# buck3.net
KiCad netlist of a schematic drawn in Altium Designer
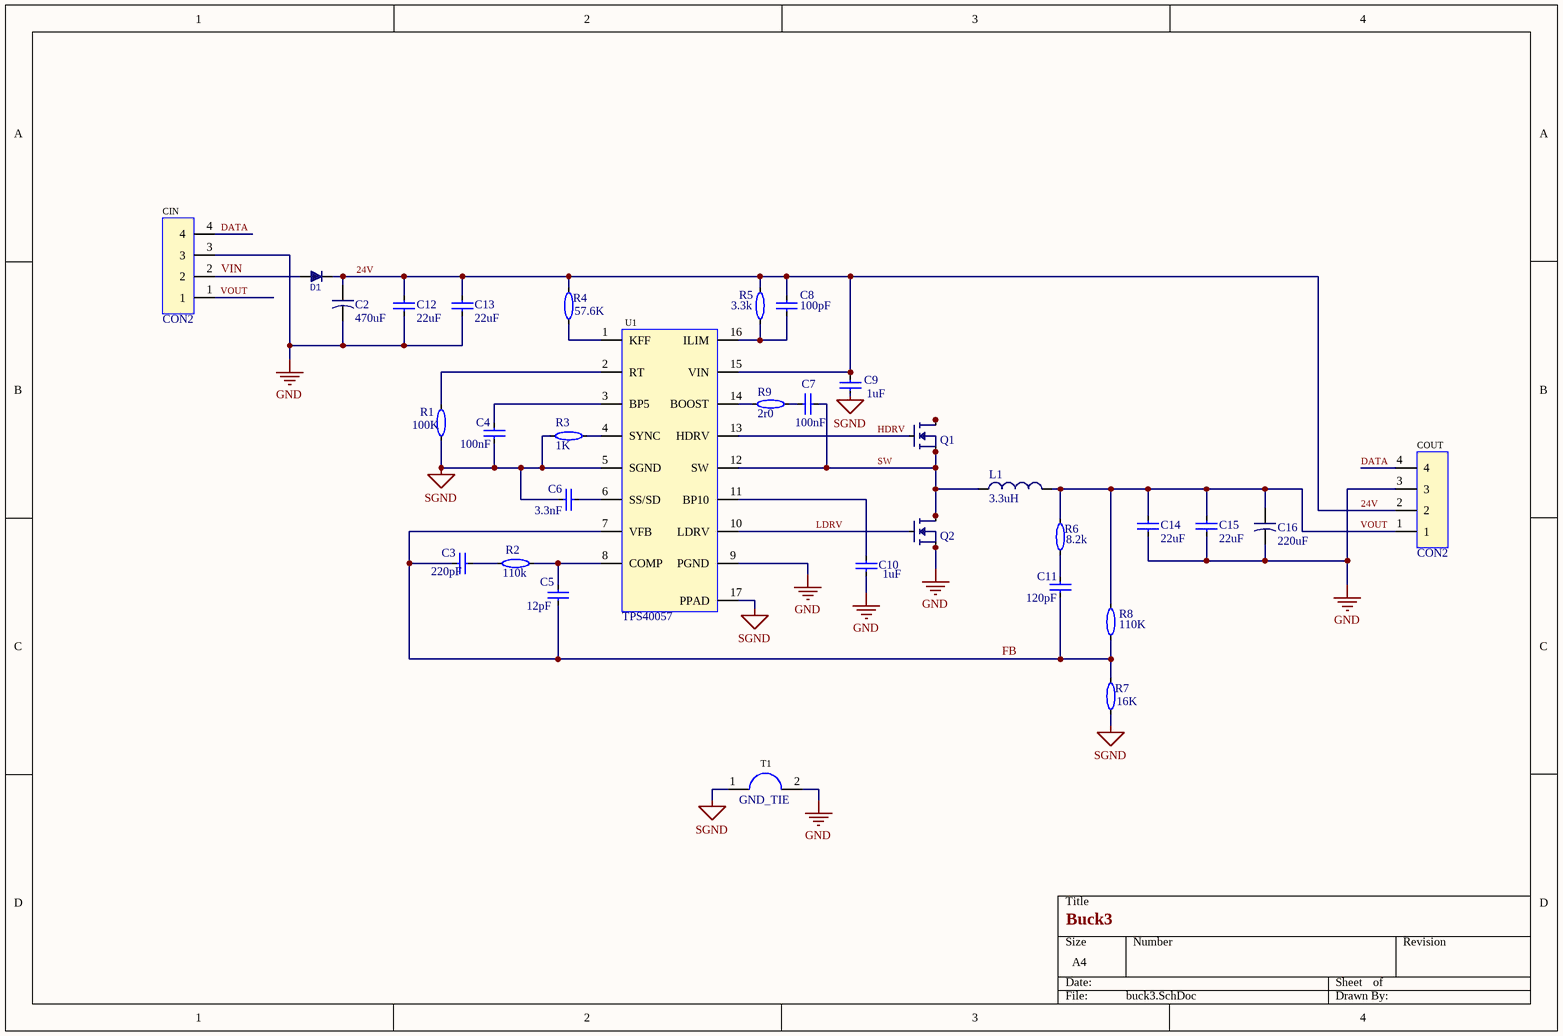
[diagram p0: buck3.SchDoc]

(export (version "E")
  (design (tool "Eeschema 10.0.6"))
  (components
    (comp (ref "C2")
      (value "470uF")
      (footprint "CAPAE110103X125L")
      (description "Capacitor")
      (libsource (lib "buck3") (part "E CAP"))
    )
    (comp (ref "C3")
      (value "220pF")
      (footprint "CAPC 0603 1608X05L")
      (description "Capacitor")
      (fields (field (name "PUBLISHER") "Altium Limited"))
      (libsource (lib "buck3") (part "Cap"))
    )
    (comp (ref "C4")
      (value "100nF")
      (footprint "CAPC 0603 1608X05L")
      (description "Capacitor")
      (fields (field (name "PUBLISHER") "Altium Limited"))
      (libsource (lib "buck3") (part "Cap"))
    )
    (comp (ref "C5")
      (value "12pF")
      (footprint "CAPC 0603 1608X05L")
      (description "Capacitor")
      (fields (field (name "PUBLISHER") "Altium Limited"))
      (libsource (lib "buck3") (part "Cap"))
    )
    (comp (ref "C6")
      (value "3.3nF")
      (footprint "CAPC 0603 1608X05L")
      (description "Capacitor")
      (fields (field (name "PUBLISHER") "Altium Limited"))
      (libsource (lib "buck3") (part "Cap"))
    )
    (comp (ref "C7")
      (value "100nF")
      (footprint "CAPC 0603 1608X05L")
      (description "Capacitor")
      (fields (field (name "PUBLISHER") "Altium Limited"))
      (libsource (lib "buck3") (part "Cap"))
    )
    (comp (ref "C8")
      (value "100pF")
      (footprint "CAPC 0603 1608X05L")
      (description "Capacitor")
      (fields (field (name "PUBLISHER") "Altium Limited"))
      (libsource (lib "buck3") (part "Cap"))
    )
    (comp (ref "C9")
      (value "1uF")
      (footprint "CAPC 0603 1608X05L")
      (description "Capacitor")
      (fields (field (name "PUBLISHER") "Altium Limited"))
      (libsource (lib "buck3") (part "Cap"))
    )
    (comp (ref "C10")
      (value "1uF")
      (footprint "CAPC 0603 1608X05L")
      (description "Capacitor")
      (fields (field (name "PUBLISHER") "Altium Limited"))
      (libsource (lib "buck3") (part "Cap"))
    )
    (comp (ref "C11")
      (value "120pF")
      (footprint "CAPC 0603 1608X05L")
      (description "Capacitor")
      (fields (field (name "PUBLISHER") "Altium Limited"))
      (libsource (lib "buck3") (part "Cap"))
    )
    (comp (ref "C12")
      (value "22uF")
      (footprint "CAPC 1210")
      (description "Capacitor")
      (fields (field (name "PUBLISHER") "Altium Limited"))
      (libsource (lib "buck3") (part "Cap"))
    )
    (comp (ref "C13")
      (value "22uF")
      (footprint "CAPC 1210")
      (description "Capacitor")
      (fields (field (name "PUBLISHER") "Altium Limited"))
      (libsource (lib "buck3") (part "Cap"))
    )
    (comp (ref "C14")
      (value "22uF")
      (footprint "CAPC 1210")
      (description "Capacitor")
      (fields (field (name "PUBLISHER") "Altium Limited"))
      (libsource (lib "buck3") (part "Cap"))
    )
    (comp (ref "C15")
      (value "22uF")
      (footprint "CAPC 1210")
      (description "Capacitor")
      (fields (field (name "PUBLISHER") "Altium Limited"))
      (libsource (lib "buck3") (part "Cap"))
    )
    (comp (ref "C16")
      (value "220uF")
      (footprint "CAPAE110103X125L")
      (description "Capacitor")
      (libsource (lib "buck3") (part "E CAP"))
    )
    (comp (ref "CIN") (value "CON2") (footprint "CON2") (libsource (lib "buck3") (part "CON2")))
    (comp (ref "COUT") (value "CON2") (footprint "CON2") (libsource (lib "") (part "CON2_1")))
    (comp (ref "D1") (value "DIODE") (footprint "SODFL350X110-2N") (libsource (lib "buck3") (part "DIODE")))
    (comp (ref "L1")
      (value "3.3uH")
      (footprint "INDP135126X40L")
      (description "Inductor")
      (fields (field (name "PUBLISHER") "Altium Limited"))
      (libsource (lib "buck3") (part "Inductor"))
    )
    (comp (ref "Q1")
      (value "Infineon BSC093N04LSGATMA1")
      (footprint "INF-PG-TDSON-8-1_V")
      (description "N Channel MOSFET")
      (libsource (lib "buck3") (part "MOSFET-N"))
    )
    (comp (ref "Q2")
      (value "Infineon BSC093N04LSGATMA1")
      (footprint "INF-PG-TDSON-8-1_V")
      (description "N Channel MOSFET")
      (libsource (lib "buck3") (part "MOSFET-N"))
    )
    (comp (ref "R1")
      (value "100K")
      (footprint "RESC 0603 1608X05L")
      (description "Resistor")
      (fields (field (name "PUBLISHER") "Altium Limited"))
      (libsource (lib "buck3") (part "Res2"))
    )
    (comp (ref "R2")
      (value "110k")
      (footprint "RESC 0603 1608X05L")
      (description "Resistor")
      (fields (field (name "PUBLISHER") "Altium Limited"))
      (libsource (lib "buck3") (part "Res2"))
    )
    (comp (ref "R3")
      (value "1K")
      (footprint "RESC 0603 1608X05L")
      (description "Resistor")
      (fields (field (name "PUBLISHER") "Altium Limited"))
      (libsource (lib "buck3") (part "Res2"))
    )
    (comp (ref "R4")
      (value "57.6K")
      (footprint "RESC 0603 1608X05L")
      (description "Resistor")
      (fields (field (name "PUBLISHER") "Altium Limited"))
      (libsource (lib "buck3") (part "Res2"))
    )
    (comp (ref "R5")
      (value "3.3k")
      (footprint "RESC 0603 1608X05L")
      (description "Resistor")
      (fields (field (name "PUBLISHER") "Altium Limited"))
      (libsource (lib "buck3") (part "Res2"))
    )
    (comp (ref "R6")
      (value "8.2k")
      (footprint "RESC 0603 1608X05L")
      (description "Resistor")
      (fields (field (name "PUBLISHER") "Altium Limited"))
      (libsource (lib "buck3") (part "Res2"))
    )
    (comp (ref "R7")
      (value "16K")
      (footprint "RESC 0603 1608X05L")
      (description "Resistor")
      (fields (field (name "PUBLISHER") "Altium Limited"))
      (libsource (lib "buck3") (part "Res2"))
    )
    (comp (ref "R8")
      (value "110K")
      (footprint "RESC 0603 1608X05L")
      (description "Resistor")
      (fields (field (name "PUBLISHER") "Altium Limited"))
      (libsource (lib "buck3") (part "Res2"))
    )
    (comp (ref "R9")
      (value "2r0")
      (footprint "RESC 0603 1608X05L")
      (description "Resistor")
      (fields (field (name "PUBLISHER") "Altium Limited"))
      (libsource (lib "buck3") (part "Res2"))
    )
    (comp (ref "T1") (value "GND_TIE") (footprint "GND_TIE") (libsource (lib "buck3") (part "GND_TIE")))
    (comp (ref "U1")
      (value "TPS40057")
      (footprint "TSOP65P640X120_HS-17N")
      (description "Buck Controller")
      (libsource (lib "buck3") (part "TPS40057"))
    )
  )
  (nets
    (net (code "1") (name "/24V") (class "Default")
      (node (ref "C12") (pin "2") (pinfunction "2_2") (pintype "passive"))
      (node (ref "C13") (pin "2") (pinfunction "2_2") (pintype "passive"))
      (node (ref "C2") (pin "1") (pinfunction "1_1") (pintype "passive"))
      (node (ref "C8") (pin "2") (pinfunction "2_2") (pintype "passive"))
      (node (ref "C9") (pin "2") (pinfunction "2_2") (pintype "passive"))
      (node (ref "COUT") (pin "2") (pinfunction "2_2") (pintype "passive"))
      (node (ref "D1") (pin "1") (pinfunction "CATHODE_1") (pintype "power_in"))
      (node (ref "R4") (pin "1") (pinfunction "1_1") (pintype "passive"))
      (node (ref "R5") (pin "1") (pinfunction "1_1") (pintype "passive"))
      (node (ref "U1") (pin "15") (pinfunction "VIN_15") (pintype "passive"))
    )
    (net (code "2") (name "/DATA") (class "Default")
      (node (ref "CIN") (pin "4") (pinfunction "4_4") (pintype "passive"))
      (node (ref "COUT") (pin "4") (pinfunction "4_4") (pintype "passive"))
    )
    (net (code "3") (name "/FB") (class "Default")
      (node (ref "C11") (pin "2") (pinfunction "2_2") (pintype "passive"))
      (node (ref "C3") (pin "2") (pinfunction "2_2") (pintype "passive"))
      (node (ref "C5") (pin "2") (pinfunction "2_2") (pintype "passive"))
      (node (ref "R7") (pin "2") (pinfunction "2_2") (pintype "passive"))
      (node (ref "R8") (pin "1") (pinfunction "1_1") (pintype "passive"))
      (node (ref "U1") (pin "7") (pinfunction "VFB_7") (pintype "passive"))
    )
    (net (code "4") (name "/HDRV") (class "Default")
      (node (ref "Q1") (pin "4") (pinfunction "G_4") (pintype "passive"))
      (node (ref "U1") (pin "13") (pinfunction "HDRV_13") (pintype "passive"))
    )
    (net (code "5") (name "/LDRV") (class "Default")
      (node (ref "Q2") (pin "4") (pinfunction "G_4") (pintype "passive"))
      (node (ref "U1") (pin "10") (pinfunction "LDRV_10") (pintype "passive"))
    )
    (net (code "6") (name "/SW") (class "Default")
      (node (ref "C7") (pin "1") (pinfunction "1_1") (pintype "passive"))
      (node (ref "L1") (pin "1") (pinfunction "1_1") (pintype "passive"))
      (node (ref "Q1") (pin "1") (pinfunction "S_1") (pintype "passive"))
      (node (ref "Q1") (pin "2") (pinfunction "S_2") (pintype "passive"))
      (node (ref "Q1") (pin "3") (pinfunction "S_3") (pintype "passive"))
      (node (ref "Q2") (pin "5") (pinfunction "D_5") (pintype "passive"))
      (node (ref "Q2") (pin "6") (pinfunction "D_6") (pintype "passive"))
      (node (ref "Q2") (pin "7") (pinfunction "D_7") (pintype "passive"))
      (node (ref "Q2") (pin "8") (pinfunction "8_8") (pintype "passive"))
      (node (ref "U1") (pin "12") (pinfunction "SW_12") (pintype "passive"))
    )
    (net (code "7") (name "/VIN") (class "Default")
      (node (ref "CIN") (pin "2") (pinfunction "2_2") (pintype "passive"))
      (node (ref "D1") (pin "2") (pinfunction "ANODE_2") (pintype "power_in"))
    )
    (net (code "8") (name "/VOUT") (class "Default")
      (node (ref "C14") (pin "2") (pinfunction "2_2") (pintype "passive"))
      (node (ref "C15") (pin "2") (pinfunction "2_2") (pintype "passive"))
      (node (ref "C16") (pin "1") (pinfunction "1_1") (pintype "passive"))
      (node (ref "CIN") (pin "1") (pinfunction "1_1") (pintype "passive"))
      (node (ref "COUT") (pin "1") (pinfunction "1_1") (pintype "passive"))
      (node (ref "L1") (pin "2") (pinfunction "2_2") (pintype "passive"))
      (node (ref "R6") (pin "2") (pinfunction "2_2") (pintype "passive"))
      (node (ref "R8") (pin "2") (pinfunction "2_2") (pintype "passive"))
    )
    (net (code "9") (name "GND") (class "Default")
      (node (ref "C10") (pin "1") (pinfunction "1_1") (pintype "passive"))
      (node (ref "C12") (pin "1") (pinfunction "1_1") (pintype "passive"))
      (node (ref "C13") (pin "1") (pinfunction "1_1") (pintype "passive"))
      (node (ref "C14") (pin "1") (pinfunction "1_1") (pintype "passive"))
      (node (ref "C15") (pin "1") (pinfunction "1_1") (pintype "passive"))
      (node (ref "C16") (pin "2") (pinfunction "2_2") (pintype "passive"))
      (node (ref "C2") (pin "2") (pinfunction "2_2") (pintype "passive"))
      (node (ref "CIN") (pin "3") (pinfunction "3_3") (pintype "passive"))
      (node (ref "COUT") (pin "3") (pinfunction "3_3") (pintype "passive"))
      (node (ref "Q2") (pin "1") (pinfunction "S_1") (pintype "passive"))
      (node (ref "Q2") (pin "2") (pinfunction "S_2") (pintype "passive"))
      (node (ref "Q2") (pin "3") (pinfunction "S_3") (pintype "passive"))
      (node (ref "T1") (pin "2") (pinfunction "2_2") (pintype "passive"))
      (node (ref "U1") (pin "9") (pinfunction "PGND_9") (pintype "passive"))
    )
    (net (code "10") (name "Net-(C3-Pad1)") (class "Default")
      (node (ref "C3") (pin "1") (pinfunction "1_1") (pintype "passive"))
      (node (ref "R2") (pin "1") (pinfunction "1_1") (pintype "passive"))
    )
    (net (code "11") (name "Net-(C7-Pad2)") (class "Default")
      (node (ref "C7") (pin "2") (pinfunction "2_2") (pintype "passive"))
      (node (ref "R9") (pin "2") (pinfunction "2_2") (pintype "passive"))
    )
    (net (code "12") (name "Net-(C11-Pad1)") (class "Default")
      (node (ref "C11") (pin "1") (pinfunction "1_1") (pintype "passive"))
      (node (ref "R6") (pin "1") (pinfunction "1_1") (pintype "passive"))
    )
    (net (code "13") (name "Net-(Q1-D-Pad5)") (class "Default")
      (node (ref "Q1") (pin "5") (pinfunction "D_5") (pintype "passive"))
      (node (ref "Q1") (pin "6") (pinfunction "D_6") (pintype "passive"))
      (node (ref "Q1") (pin "7") (pinfunction "D_7") (pintype "passive"))
      (node (ref "Q1") (pin "8") (pinfunction "8_8") (pintype "passive"))
    )
    (net (code "14") (name "Net-(U1-BOOST)") (class "Default")
      (node (ref "R9") (pin "1") (pinfunction "1_1") (pintype "passive"))
      (node (ref "U1") (pin "14") (pinfunction "BOOST_14") (pintype "passive"))
    )
    (net (code "15") (name "Net-(U1-BP5)") (class "Default")
      (node (ref "C4") (pin "2") (pinfunction "2_2") (pintype "passive"))
      (node (ref "U1") (pin "3") (pinfunction "BP5_3") (pintype "passive"))
    )
    (net (code "16") (name "Net-(U1-BP10)") (class "Default")
      (node (ref "C10") (pin "2") (pinfunction "2_2") (pintype "passive"))
      (node (ref "U1") (pin "11") (pinfunction "BP10_11") (pintype "passive"))
    )
    (net (code "17") (name "Net-(U1-COMP)") (class "Default")
      (node (ref "C5") (pin "1") (pinfunction "1_1") (pintype "passive"))
      (node (ref "R2") (pin "2") (pinfunction "2_2") (pintype "passive"))
      (node (ref "U1") (pin "8") (pinfunction "COMP_8") (pintype "passive"))
    )
    (net (code "18") (name "Net-(U1-ILIM)") (class "Default")
      (node (ref "C8") (pin "1") (pinfunction "1_1") (pintype "passive"))
      (node (ref "R5") (pin "2") (pinfunction "2_2") (pintype "passive"))
      (node (ref "U1") (pin "16") (pinfunction "ILIM_16") (pintype "passive"))
    )
    (net (code "19") (name "Net-(U1-KFF)") (class "Default")
      (node (ref "R4") (pin "2") (pinfunction "2_2") (pintype "passive"))
      (node (ref "U1") (pin "1") (pinfunction "KFF_1") (pintype "passive"))
    )
    (net (code "20") (name "Net-(U1-RT)") (class "Default")
      (node (ref "R1") (pin "2") (pinfunction "2_2") (pintype "passive"))
      (node (ref "U1") (pin "2") (pinfunction "RT_2") (pintype "passive"))
    )
    (net (code "21") (name "Net-(U1-SS{slash}SD)") (class "Default")
      (node (ref "C6") (pin "2") (pinfunction "2_2") (pintype "passive"))
      (node (ref "U1") (pin "6") (pinfunction "SS/SD_6") (pintype "passive"))
    )
    (net (code "22") (name "Net-(U1-SYNC)") (class "Default")
      (node (ref "R3") (pin "2") (pinfunction "2_2") (pintype "passive"))
      (node (ref "U1") (pin "4") (pinfunction "SYNC_4") (pintype "passive"))
    )
    (net (code "23") (name "SGND") (class "Default")
      (node (ref "C4") (pin "1") (pinfunction "1_1") (pintype "passive"))
      (node (ref "C6") (pin "1") (pinfunction "1_1") (pintype "passive"))
      (node (ref "C9") (pin "1") (pinfunction "1_1") (pintype "passive"))
      (node (ref "R1") (pin "1") (pinfunction "1_1") (pintype "passive"))
      (node (ref "R3") (pin "1") (pinfunction "1_1") (pintype "passive"))
      (node (ref "R7") (pin "1") (pinfunction "1_1") (pintype "passive"))
      (node (ref "T1") (pin "1") (pinfunction "1_1") (pintype "passive"))
      (node (ref "U1") (pin "17") (pinfunction "PPAD_17") (pintype "passive"))
      (node (ref "U1") (pin "5") (pinfunction "SGND_5") (pintype "passive"))
    )
  )
)
